# Uebersicht.net
KiCad netlist of a schematic drawn in Altium Designer
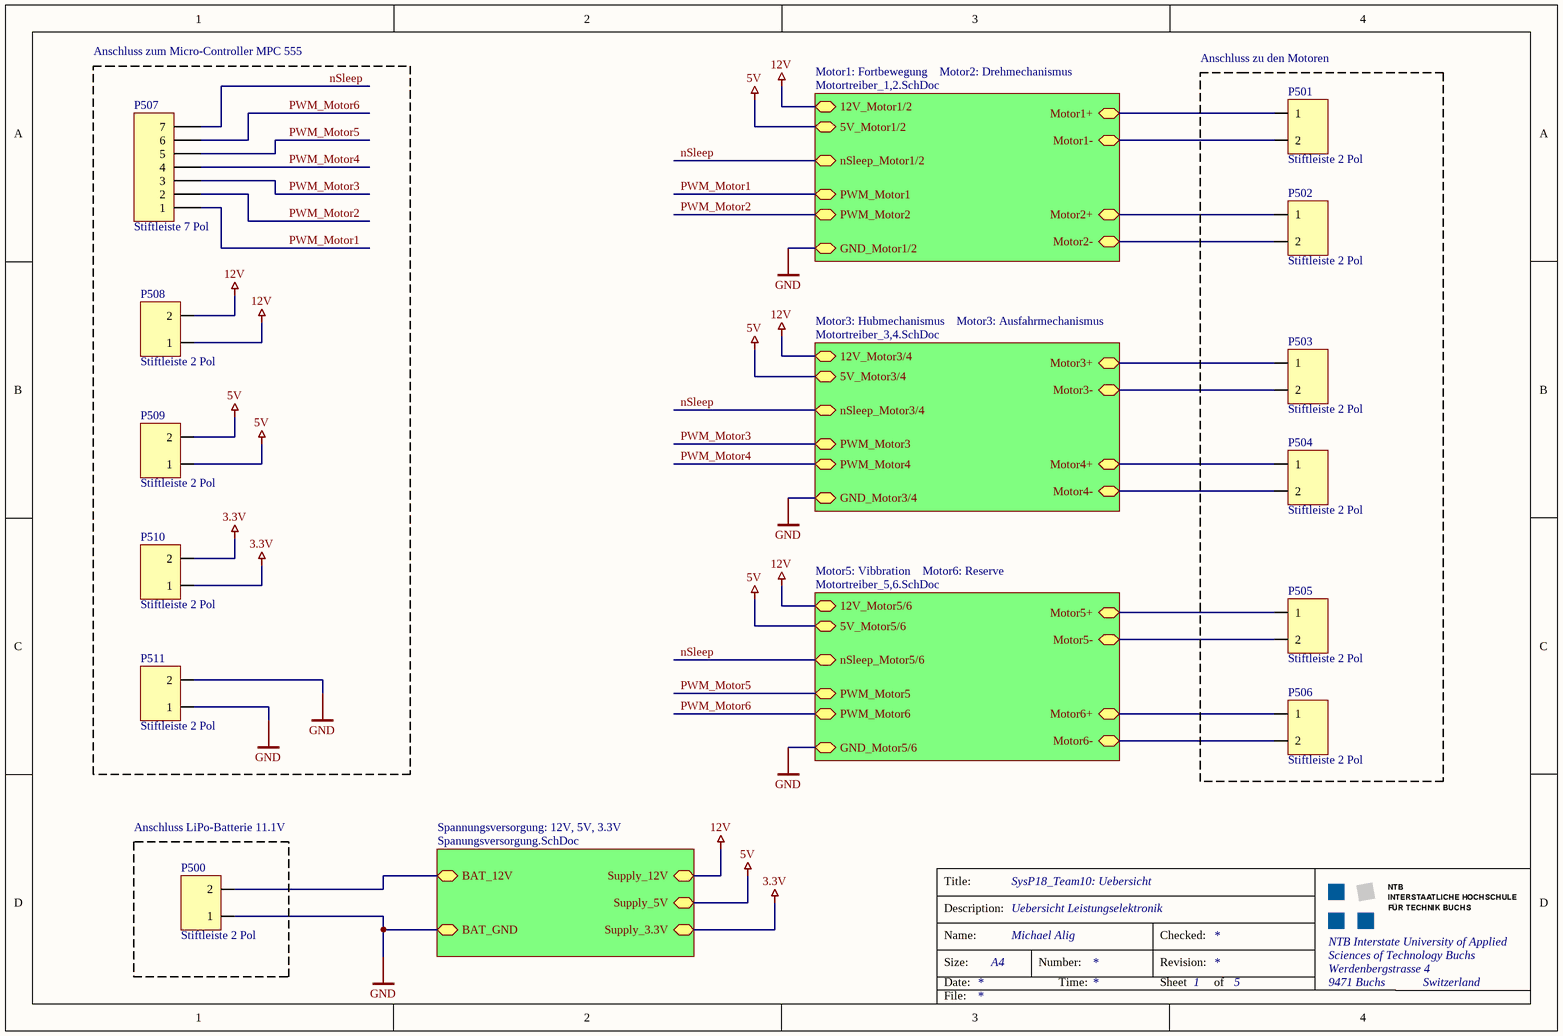
[diagram p0: Uebersicht.SchDoc]

(export (version "E")
  (design (tool "Eeschema 10.0.6"))
  (components
    (comp (ref "P500")
      (value "Stiftleiste 2 Pol")
      (footprint "2Pin Header 2.54mm")
      (description "2 Pin Header 2.54mm")
      (libsource (lib "Motorentreiber") (part "2 Pin Connector"))
    )
    (comp (ref "P501")
      (value "Stiftleiste 2 Pol")
      (footprint "2Pin Header 2.54mm")
      (description "2 Pin Header 2.54mm")
      (libsource (lib "") (part "2 Pin Connector_1"))
    )
    (comp (ref "P502")
      (value "Stiftleiste 2 Pol")
      (footprint "2Pin Header 2.54mm")
      (description "2 Pin Header 2.54mm")
      (libsource (lib "") (part "2 Pin Connector_1"))
    )
    (comp (ref "P503")
      (value "Stiftleiste 2 Pol")
      (footprint "2Pin Header 2.54mm")
      (description "2 Pin Header 2.54mm")
      (libsource (lib "") (part "2 Pin Connector_1"))
    )
    (comp (ref "P504")
      (value "Stiftleiste 2 Pol")
      (footprint "2Pin Header 2.54mm")
      (description "2 Pin Header 2.54mm")
      (libsource (lib "") (part "2 Pin Connector_1"))
    )
    (comp (ref "P505")
      (value "Stiftleiste 2 Pol")
      (footprint "2Pin Header 2.54mm")
      (description "2 Pin Header 2.54mm")
      (libsource (lib "") (part "2 Pin Connector_1"))
    )
    (comp (ref "P506")
      (value "Stiftleiste 2 Pol")
      (footprint "2Pin Header 2.54mm")
      (description "2 Pin Header 2.54mm")
      (libsource (lib "") (part "2 Pin Connector_1"))
    )
    (comp (ref "P507")
      (value "Stiftleiste 7 Pol")
      (footprint "GEN_HEADER-2.54mm_7_H")
      (description "generic Header, 7-Pin")
      (fields (field (name "MANUFACTURER") "tbd") (field (name "PUBLISHER") "Altium Limited"))
      (libsource (lib "Motorentreiber") (part "GEN_HEADER_7"))
    )
    (comp (ref "P508")
      (value "Stiftleiste 2 Pol")
      (footprint "2Pin Header 2.54mm")
      (description "2 Pin Header 2.54mm")
      (libsource (lib "Motorentreiber") (part "2 Pin Connector"))
    )
    (comp (ref "P509")
      (value "Stiftleiste 2 Pol")
      (footprint "2Pin Header 2.54mm")
      (description "2 Pin Header 2.54mm")
      (libsource (lib "Motorentreiber") (part "2 Pin Connector"))
    )
    (comp (ref "P510")
      (value "Stiftleiste 2 Pol")
      (footprint "2Pin Header 2.54mm")
      (description "2 Pin Header 2.54mm")
      (libsource (lib "Motorentreiber") (part "2 Pin Connector"))
    )
    (comp (ref "P511")
      (value "Stiftleiste 2 Pol")
      (footprint "2Pin Header 2.54mm")
      (description "2 Pin Header 2.54mm")
      (libsource (lib "Motorentreiber") (part "2 Pin Connector"))
    )
  )
  (nets
    (net (code "1") (name "/BAT_12V") (class "Default")
      (node (ref "P500") (pin "2") (pinfunction "2_2") (pintype "passive"))
    )
    (net (code "2") (name "/Motor1+") (class "Default")
      (node (ref "P501") (pin "1") (pinfunction "1_1") (pintype "passive"))
    )
    (net (code "3") (name "/Motor1-") (class "Default")
      (node (ref "P501") (pin "2") (pinfunction "2_2") (pintype "passive"))
    )
    (net (code "4") (name "/Motor2+") (class "Default")
      (node (ref "P502") (pin "1") (pinfunction "1_1") (pintype "passive"))
    )
    (net (code "5") (name "/Motor2-") (class "Default")
      (node (ref "P502") (pin "2") (pinfunction "2_2") (pintype "passive"))
    )
    (net (code "6") (name "/Motor3+") (class "Default")
      (node (ref "P503") (pin "1") (pinfunction "1_1") (pintype "passive"))
    )
    (net (code "7") (name "/Motor3-") (class "Default")
      (node (ref "P503") (pin "2") (pinfunction "2_2") (pintype "passive"))
    )
    (net (code "8") (name "/Motor4+") (class "Default")
      (node (ref "P504") (pin "1") (pinfunction "1_1") (pintype "passive"))
    )
    (net (code "9") (name "/Motor4-") (class "Default")
      (node (ref "P504") (pin "2") (pinfunction "2_2") (pintype "passive"))
    )
    (net (code "10") (name "/Motor5+") (class "Default")
      (node (ref "P505") (pin "1") (pinfunction "1_1") (pintype "passive"))
    )
    (net (code "11") (name "/Motor5-") (class "Default")
      (node (ref "P505") (pin "2") (pinfunction "2_2") (pintype "passive"))
    )
    (net (code "12") (name "/Motor6+") (class "Default")
      (node (ref "P506") (pin "1") (pinfunction "1_1") (pintype "passive"))
    )
    (net (code "13") (name "/Motor6-") (class "Default")
      (node (ref "P506") (pin "2") (pinfunction "2_2") (pintype "passive"))
    )
    (net (code "14") (name "/PWM_Motor1") (class "Default")
      (node (ref "P507") (pin "1") (pinfunction "1_1") (pintype "passive"))
    )
    (net (code "15") (name "/PWM_Motor2") (class "Default")
      (node (ref "P507") (pin "2") (pinfunction "2_2") (pintype "passive"))
    )
    (net (code "16") (name "/PWM_Motor3") (class "Default")
      (node (ref "P507") (pin "3") (pinfunction "3_3") (pintype "passive"))
    )
    (net (code "17") (name "/PWM_Motor4") (class "Default")
      (node (ref "P507") (pin "4") (pinfunction "4_4") (pintype "passive"))
    )
    (net (code "18") (name "/PWM_Motor5") (class "Default")
      (node (ref "P507") (pin "5") (pinfunction "5_5") (pintype "passive"))
    )
    (net (code "19") (name "/PWM_Motor6") (class "Default")
      (node (ref "P507") (pin "6") (pinfunction "6_6") (pintype "passive"))
    )
    (net (code "20") (name "/nSleep") (class "Default")
      (node (ref "P507") (pin "7") (pinfunction "7_7") (pintype "passive"))
    )
    (net (code "21") (name "3.3V") (class "Default")
      (node (ref "P510") (pin "1") (pinfunction "1_1") (pintype "passive"))
      (node (ref "P510") (pin "2") (pinfunction "2_2") (pintype "passive"))
    )
    (net (code "22") (name "5V") (class "Default")
      (node (ref "P509") (pin "1") (pinfunction "1_1") (pintype "passive"))
      (node (ref "P509") (pin "2") (pinfunction "2_2") (pintype "passive"))
    )
    (net (code "23") (name "12V") (class "Default")
      (node (ref "P508") (pin "1") (pinfunction "1_1") (pintype "passive"))
      (node (ref "P508") (pin "2") (pinfunction "2_2") (pintype "passive"))
    )
    (net (code "24") (name "GND") (class "Default")
      (node (ref "P500") (pin "1") (pinfunction "1_1") (pintype "passive"))
      (node (ref "P511") (pin "1") (pinfunction "1_1") (pintype "passive"))
      (node (ref "P511") (pin "2") (pinfunction "2_2") (pintype "passive"))
    )
  )
)
